# RTL8211.net
KiCad netlist of a schematic drawn in Altium Designer
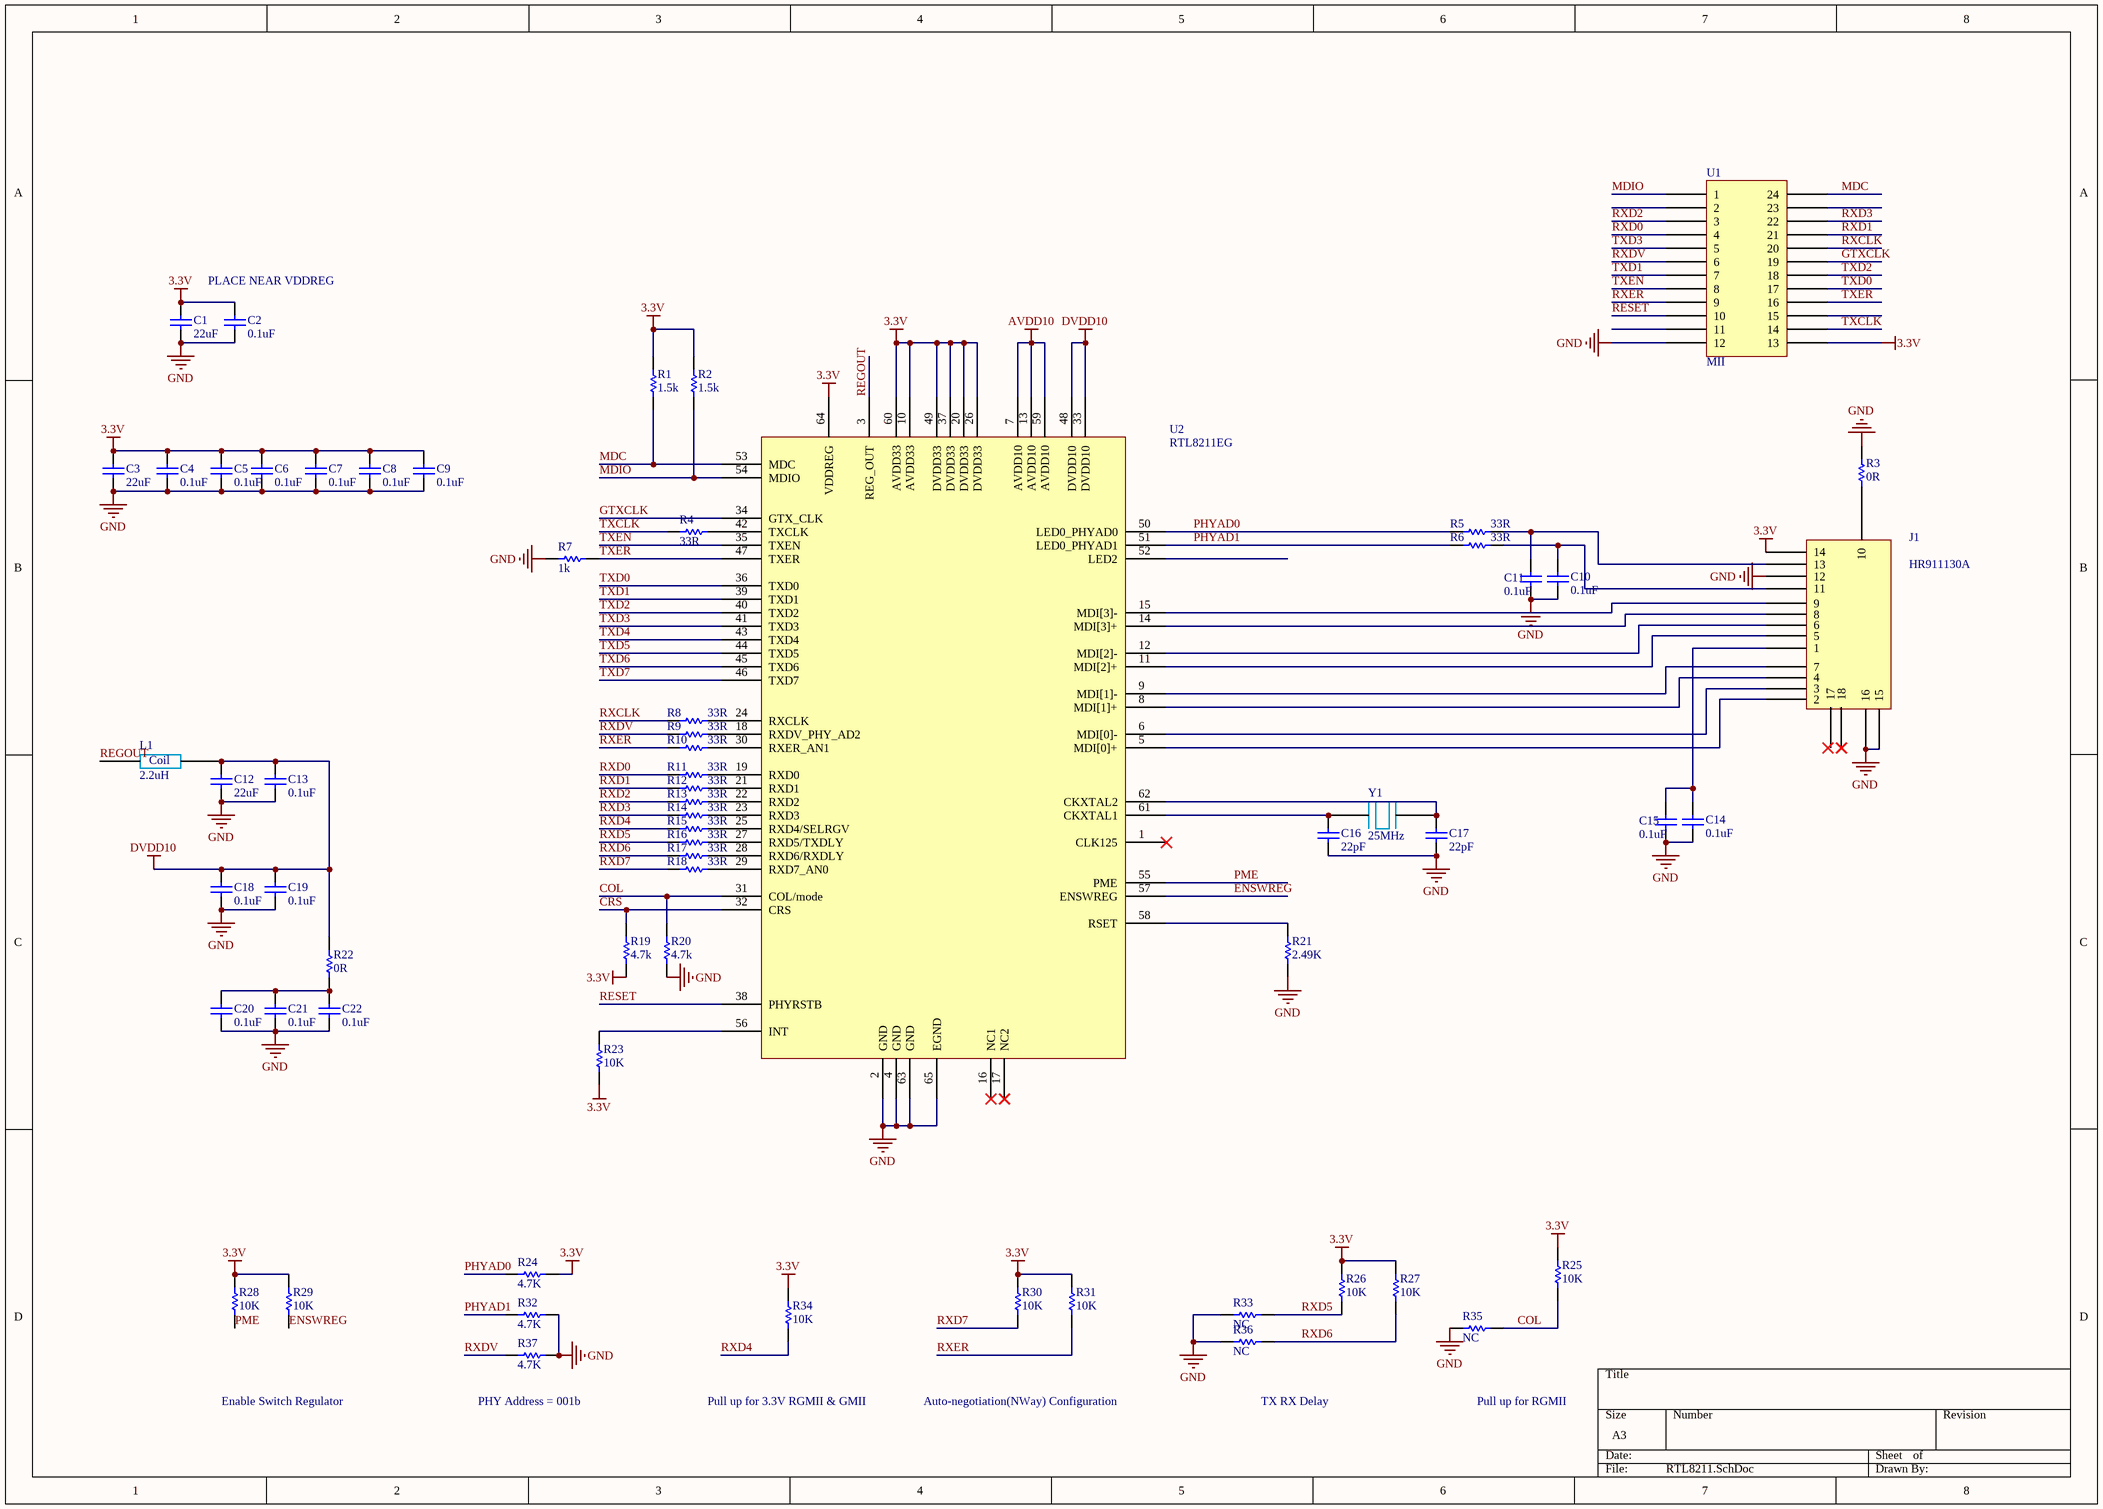
[diagram p0: RTL8211.SchDoc]

(export (version "E")
  (design (tool "Eeschema 10.0.6"))
  (components
    (comp (ref "C1")
      (value "22uF")
      (footprint "0805C")
      (description "Capacitor")
      (fields (field (name "PUBLISHER") "Altium Limited"))
      (libsource (lib "AutoCAN") (part "Cap"))
    )
    (comp (ref "C2")
      (value "0.1uF")
      (footprint "0805C")
      (description "Capacitor")
      (fields (field (name "PUBLISHER") "Altium Limited"))
      (libsource (lib "AutoCAN") (part "Cap"))
    )
    (comp (ref "C3")
      (value "22uF")
      (footprint "0805C")
      (description "Capacitor")
      (fields (field (name "PUBLISHER") "Altium Limited"))
      (libsource (lib "AutoCAN") (part "Cap"))
    )
    (comp (ref "C4")
      (value "0.1uF")
      (footprint "0805C")
      (description "Capacitor")
      (fields (field (name "PUBLISHER") "Altium Limited"))
      (libsource (lib "AutoCAN") (part "Cap"))
    )
    (comp (ref "C5")
      (value "0.1uF")
      (footprint "0805C")
      (description "Capacitor")
      (fields (field (name "PUBLISHER") "Altium Limited"))
      (libsource (lib "AutoCAN") (part "Cap"))
    )
    (comp (ref "C6")
      (value "0.1uF")
      (footprint "0805C")
      (description "Capacitor")
      (fields (field (name "PUBLISHER") "Altium Limited"))
      (libsource (lib "AutoCAN") (part "Cap"))
    )
    (comp (ref "C7")
      (value "0.1uF")
      (footprint "0805C")
      (description "Capacitor")
      (fields (field (name "PUBLISHER") "Altium Limited"))
      (libsource (lib "AutoCAN") (part "Cap"))
    )
    (comp (ref "C8")
      (value "0.1uF")
      (footprint "0805C")
      (description "Capacitor")
      (fields (field (name "PUBLISHER") "Altium Limited"))
      (libsource (lib "AutoCAN") (part "Cap"))
    )
    (comp (ref "C9")
      (value "0.1uF")
      (footprint "0805C")
      (description "Capacitor")
      (fields (field (name "PUBLISHER") "Altium Limited"))
      (libsource (lib "AutoCAN") (part "Cap"))
    )
    (comp (ref "C10")
      (value "0.1uF")
      (footprint "0805C")
      (description "Capacitor")
      (fields (field (name "PUBLISHER") "Altium Limited"))
      (libsource (lib "AutoCAN") (part "Cap"))
    )
    (comp (ref "C11")
      (value "0.1uF")
      (footprint "0805C")
      (description "Capacitor")
      (fields (field (name "PUBLISHER") "Altium Limited"))
      (libsource (lib "AutoCAN") (part "Cap"))
    )
    (comp (ref "C12")
      (value "22uF")
      (footprint "0805C")
      (description "Capacitor")
      (fields (field (name "PUBLISHER") "Altium Limited"))
      (libsource (lib "AutoCAN") (part "Cap"))
    )
    (comp (ref "C13")
      (value "0.1uF")
      (footprint "0805C")
      (description "Capacitor")
      (fields (field (name "PUBLISHER") "Altium Limited"))
      (libsource (lib "AutoCAN") (part "Cap"))
    )
    (comp (ref "C14")
      (value "0.1uF")
      (footprint "0805C")
      (description "Capacitor")
      (fields (field (name "PUBLISHER") "Altium Limited"))
      (libsource (lib "AutoCAN") (part "Cap"))
    )
    (comp (ref "C15")
      (value "0.1uF")
      (footprint "0805C")
      (description "Capacitor")
      (fields (field (name "PUBLISHER") "Altium Limited"))
      (libsource (lib "AutoCAN") (part "Cap"))
    )
    (comp (ref "C16")
      (value "22pF")
      (footprint "0805C")
      (description "Capacitor")
      (fields (field (name "PUBLISHER") "Altium Limited"))
      (libsource (lib "AutoCAN") (part "Cap"))
    )
    (comp (ref "C17")
      (value "22pF")
      (footprint "0805C")
      (description "Capacitor")
      (fields (field (name "PUBLISHER") "Altium Limited"))
      (libsource (lib "AutoCAN") (part "Cap"))
    )
    (comp (ref "C18")
      (value "0.1uF")
      (footprint "0805C")
      (description "Capacitor")
      (fields (field (name "PUBLISHER") "Altium Limited"))
      (libsource (lib "AutoCAN") (part "Cap"))
    )
    (comp (ref "C19")
      (value "0.1uF")
      (footprint "0805C")
      (description "Capacitor")
      (fields (field (name "PUBLISHER") "Altium Limited"))
      (libsource (lib "AutoCAN") (part "Cap"))
    )
    (comp (ref "C20")
      (value "0.1uF")
      (footprint "0805C")
      (description "Capacitor")
      (fields (field (name "PUBLISHER") "Altium Limited"))
      (libsource (lib "AutoCAN") (part "Cap"))
    )
    (comp (ref "C21")
      (value "0.1uF")
      (footprint "0805C")
      (description "Capacitor")
      (fields (field (name "PUBLISHER") "Altium Limited"))
      (libsource (lib "AutoCAN") (part "Cap"))
    )
    (comp (ref "C22")
      (value "0.1uF")
      (footprint "0805C")
      (description "Capacitor")
      (fields (field (name "PUBLISHER") "Altium Limited"))
      (libsource (lib "AutoCAN") (part "Cap"))
    )
    (comp (ref "J1")
      (value "HR911130A")
      (footprint "HR911130A")
      (libsource (lib "RTL8211EG") (part "HR911130A"))
    )
    (comp (ref "L1") (value "2.2uH") (footprint "Coil") (libsource (lib "RTL8211EG") (part "Coil")))
    (comp (ref "R1")
      (value "1.5k")
      (footprint "0805")
      (description "Resistor")
      (fields (field (name "Comment") "Res") (field (name "PUBLISHER") "Altium Limited"))
      (libsource (lib "AutoCAN") (part "Res"))
    )
    (comp (ref "R2")
      (value "1.5k")
      (footprint "0805")
      (description "Resistor")
      (fields (field (name "Comment") "Res") (field (name "PUBLISHER") "Altium Limited"))
      (libsource (lib "AutoCAN") (part "Res"))
    )
    (comp (ref "R3")
      (value "0R")
      (footprint "0805")
      (description "Resistor")
      (fields (field (name "Comment") "Res") (field (name "PUBLISHER") "Altium Limited"))
      (libsource (lib "AutoCAN") (part "Res"))
    )
    (comp (ref "R4")
      (value "33R")
      (footprint "0805")
      (description "Resistor")
      (fields (field (name "Comment") "Res") (field (name "PUBLISHER") "Altium Limited"))
      (libsource (lib "AutoCAN") (part "Res"))
    )
    (comp (ref "R5")
      (value "33R")
      (footprint "0805")
      (description "Resistor")
      (fields (field (name "Comment") "Res") (field (name "PUBLISHER") "Altium Limited"))
      (libsource (lib "AutoCAN") (part "Res"))
    )
    (comp (ref "R6")
      (value "33R")
      (footprint "0805")
      (description "Resistor")
      (fields (field (name "Comment") "Res") (field (name "PUBLISHER") "Altium Limited"))
      (libsource (lib "AutoCAN") (part "Res"))
    )
    (comp (ref "R7")
      (value "1k")
      (footprint "0805")
      (description "Resistor")
      (fields (field (name "Comment") "Res") (field (name "PUBLISHER") "Altium Limited"))
      (libsource (lib "AutoCAN") (part "Res"))
    )
    (comp (ref "R8")
      (value "33R")
      (footprint "0805")
      (description "Resistor")
      (fields (field (name "Comment") "Res") (field (name "PUBLISHER") "Altium Limited"))
      (libsource (lib "AutoCAN") (part "Res"))
    )
    (comp (ref "R9")
      (value "33R")
      (footprint "0805")
      (description "Resistor")
      (fields (field (name "Comment") "Res") (field (name "PUBLISHER") "Altium Limited"))
      (libsource (lib "AutoCAN") (part "Res"))
    )
    (comp (ref "R10")
      (value "33R")
      (footprint "0805")
      (description "Resistor")
      (fields (field (name "Comment") "Res") (field (name "PUBLISHER") "Altium Limited"))
      (libsource (lib "AutoCAN") (part "Res"))
    )
    (comp (ref "R11")
      (value "33R")
      (footprint "0805")
      (description "Resistor")
      (fields (field (name "Comment") "Res") (field (name "PUBLISHER") "Altium Limited"))
      (libsource (lib "AutoCAN") (part "Res"))
    )
    (comp (ref "R12")
      (value "33R")
      (footprint "0805")
      (description "Resistor")
      (fields (field (name "Comment") "Res") (field (name "PUBLISHER") "Altium Limited"))
      (libsource (lib "AutoCAN") (part "Res"))
    )
    (comp (ref "R13")
      (value "33R")
      (footprint "0805")
      (description "Resistor")
      (fields (field (name "Comment") "Res") (field (name "PUBLISHER") "Altium Limited"))
      (libsource (lib "AutoCAN") (part "Res"))
    )
    (comp (ref "R14")
      (value "33R")
      (footprint "0805")
      (description "Resistor")
      (fields (field (name "Comment") "Res") (field (name "PUBLISHER") "Altium Limited"))
      (libsource (lib "AutoCAN") (part "Res"))
    )
    (comp (ref "R15")
      (value "33R")
      (footprint "0805")
      (description "Resistor")
      (fields (field (name "Comment") "Res") (field (name "PUBLISHER") "Altium Limited"))
      (libsource (lib "AutoCAN") (part "Res"))
    )
    (comp (ref "R16")
      (value "33R")
      (footprint "0805")
      (description "Resistor")
      (fields (field (name "Comment") "Res") (field (name "PUBLISHER") "Altium Limited"))
      (libsource (lib "AutoCAN") (part "Res"))
    )
    (comp (ref "R17")
      (value "33R")
      (footprint "0805")
      (description "Resistor")
      (fields (field (name "Comment") "Res") (field (name "PUBLISHER") "Altium Limited"))
      (libsource (lib "AutoCAN") (part "Res"))
    )
    (comp (ref "R18")
      (value "33R")
      (footprint "0805")
      (description "Resistor")
      (fields (field (name "Comment") "Res") (field (name "PUBLISHER") "Altium Limited"))
      (libsource (lib "AutoCAN") (part "Res"))
    )
    (comp (ref "R19")
      (value "4.7k")
      (footprint "0805")
      (description "Resistor")
      (fields (field (name "Comment") "Res") (field (name "PUBLISHER") "Altium Limited"))
      (libsource (lib "AutoCAN") (part "Res"))
    )
    (comp (ref "R20")
      (value "4.7k")
      (footprint "0805")
      (description "Resistor")
      (fields (field (name "Comment") "Res") (field (name "PUBLISHER") "Altium Limited"))
      (libsource (lib "AutoCAN") (part "Res"))
    )
    (comp (ref "R21")
      (value "2.49K")
      (footprint "0805")
      (description "Resistor")
      (fields (field (name "Comment") "Res") (field (name "PUBLISHER") "Altium Limited"))
      (libsource (lib "AutoCAN") (part "Res"))
    )
    (comp (ref "R22")
      (value "0R")
      (footprint "0805")
      (description "Resistor")
      (fields (field (name "Comment") "Res") (field (name "PUBLISHER") "Altium Limited"))
      (libsource (lib "AutoCAN") (part "Res"))
    )
    (comp (ref "R23")
      (value "10K")
      (footprint "0805")
      (description "Resistor")
      (fields (field (name "Comment") "Res") (field (name "PUBLISHER") "Altium Limited"))
      (libsource (lib "AutoCAN") (part "Res"))
    )
    (comp (ref "R24")
      (value "4.7K")
      (footprint "0805")
      (description "Resistor")
      (fields (field (name "Comment") "Res") (field (name "PUBLISHER") "Altium Limited"))
      (libsource (lib "AutoCAN") (part "Res"))
    )
    (comp (ref "R25")
      (value "10K")
      (footprint "0805")
      (description "Resistor")
      (fields (field (name "Comment") "Res") (field (name "PUBLISHER") "Altium Limited"))
      (libsource (lib "AutoCAN") (part "Res"))
    )
    (comp (ref "R26")
      (value "10K")
      (footprint "0805")
      (description "Resistor")
      (fields (field (name "Comment") "Res") (field (name "PUBLISHER") "Altium Limited"))
      (libsource (lib "AutoCAN") (part "Res"))
    )
    (comp (ref "R27")
      (value "10K")
      (footprint "0805")
      (description "Resistor")
      (fields (field (name "Comment") "Res") (field (name "PUBLISHER") "Altium Limited"))
      (libsource (lib "AutoCAN") (part "Res"))
    )
    (comp (ref "R28")
      (value "10K")
      (footprint "0805")
      (description "Resistor")
      (fields (field (name "Comment") "Res") (field (name "PUBLISHER") "Altium Limited"))
      (libsource (lib "AutoCAN") (part "Res"))
    )
    (comp (ref "R29")
      (value "10K")
      (footprint "0805")
      (description "Resistor")
      (fields (field (name "Comment") "Res") (field (name "PUBLISHER") "Altium Limited"))
      (libsource (lib "AutoCAN") (part "Res"))
    )
    (comp (ref "R30")
      (value "10K")
      (footprint "0805")
      (description "Resistor")
      (fields (field (name "Comment") "Res") (field (name "PUBLISHER") "Altium Limited"))
      (libsource (lib "AutoCAN") (part "Res"))
    )
    (comp (ref "R31")
      (value "10K")
      (footprint "0805")
      (description "Resistor")
      (fields (field (name "Comment") "Res") (field (name "PUBLISHER") "Altium Limited"))
      (libsource (lib "AutoCAN") (part "Res"))
    )
    (comp (ref "R32")
      (value "4.7K")
      (footprint "0805")
      (description "Resistor")
      (fields (field (name "Comment") "Res") (field (name "PUBLISHER") "Altium Limited"))
      (libsource (lib "AutoCAN") (part "Res"))
    )
    (comp (ref "R33")
      (value "NC")
      (footprint "0805")
      (description "Resistor")
      (fields (field (name "Comment") "Res") (field (name "PUBLISHER") "Altium Limited"))
      (libsource (lib "AutoCAN") (part "Res"))
    )
    (comp (ref "R34")
      (value "10K")
      (footprint "0805")
      (description "Resistor")
      (fields (field (name "Comment") "Res") (field (name "PUBLISHER") "Altium Limited"))
      (libsource (lib "AutoCAN") (part "Res"))
    )
    (comp (ref "R35")
      (value "NC")
      (footprint "0805")
      (description "Resistor")
      (fields (field (name "Comment") "Res") (field (name "PUBLISHER") "Altium Limited"))
      (libsource (lib "AutoCAN") (part "Res"))
    )
    (comp (ref "R36")
      (value "NC")
      (footprint "0805")
      (description "Resistor")
      (fields (field (name "Comment") "Res") (field (name "PUBLISHER") "Altium Limited"))
      (libsource (lib "AutoCAN") (part "Res"))
    )
    (comp (ref "R37")
      (value "4.7K")
      (footprint "0805")
      (description "Resistor")
      (fields (field (name "Comment") "Res") (field (name "PUBLISHER") "Altium Limited"))
      (libsource (lib "AutoCAN") (part "Res"))
    )
    (comp (ref "U1") (value "MII") (footprint "MII") (libsource (lib "RTL8211EG") (part "MII")))
    (comp (ref "U2")
      (value "RTL8211EG")
      (footprint "RTL8211EGQFN")
      (libsource (lib "RTL8211EG") (part "RTL8211EG"))
    )
    (comp (ref "Y1") (value "25MHz") (footprint "XTAL") (libsource (lib "RTL8211EG") (part "XTAL")))
  )
  (nets
    (net (code "1") (name "/COL") (class "Default")
      (node (ref "R20") (pin "1") (pinfunction "1_1") (pintype "passive"))
      (node (ref "R25") (pin "2") (pinfunction "2_2") (pintype "passive"))
      (node (ref "R35") (pin "2") (pinfunction "2_2") (pintype "passive"))
      (node (ref "U2") (pin "31") (pinfunction "COL/mode_31") (pintype "passive"))
    )
    (net (code "2") (name "/CRS") (class "Default")
      (node (ref "R19") (pin "1") (pinfunction "1_1") (pintype "passive"))
      (node (ref "U2") (pin "32") (pinfunction "CRS_32") (pintype "passive"))
    )
    (net (code "3") (name "/ENSWREG") (class "Default")
      (node (ref "R29") (pin "2") (pinfunction "2_2") (pintype "passive"))
      (node (ref "U2") (pin "57") (pinfunction "ENSWREG_57") (pintype "passive"))
    )
    (net (code "4") (name "/GTXCLK") (class "Default")
      (node (ref "U1") (pin "19") (pinfunction "19_19") (pintype "passive"))
      (node (ref "U2") (pin "34") (pinfunction "GTX_CLK_34") (pintype "passive"))
    )
    (net (code "5") (name "/MDC") (class "Default")
      (node (ref "R1") (pin "1") (pinfunction "1_1") (pintype "passive"))
      (node (ref "U1") (pin "24") (pinfunction "24_24") (pintype "passive"))
      (node (ref "U2") (pin "53") (pinfunction "MDC_53") (pintype "passive"))
    )
    (net (code "6") (name "/MDIO") (class "Default")
      (node (ref "R2") (pin "1") (pinfunction "1_1") (pintype "passive"))
      (node (ref "U1") (pin "1") (pinfunction "1_1") (pintype "passive"))
      (node (ref "U2") (pin "54") (pinfunction "MDIO_54") (pintype "passive"))
    )
    (net (code "7") (name "/PHYAD0") (class "Default")
      (node (ref "R24") (pin "1") (pinfunction "1_1") (pintype "passive"))
      (node (ref "R5") (pin "2") (pinfunction "2_2") (pintype "passive"))
      (node (ref "U2") (pin "50") (pinfunction "LED0_PHYAD0_50") (pintype "passive"))
    )
    (net (code "8") (name "/PHYAD1") (class "Default")
      (node (ref "R32") (pin "1") (pinfunction "1_1") (pintype "passive"))
      (node (ref "R6") (pin "2") (pinfunction "2_2") (pintype "passive"))
      (node (ref "U2") (pin "51") (pinfunction "LED0_PHYAD1_51") (pintype "passive"))
    )
    (net (code "9") (name "/PME") (class "Default")
      (node (ref "R28") (pin "2") (pinfunction "2_2") (pintype "passive"))
      (node (ref "U2") (pin "55") (pinfunction "PME_55") (pintype "passive"))
    )
    (net (code "10") (name "/REGOUT") (class "Default")
      (node (ref "L1") (pin "1") (pinfunction "1_1") (pintype "passive"))
      (node (ref "U2") (pin "3") (pinfunction "REG_OUT_3") (pintype "passive"))
    )
    (net (code "11") (name "/RESET") (class "Default")
      (node (ref "U1") (pin "10") (pinfunction "10_10") (pintype "passive"))
      (node (ref "U2") (pin "38") (pinfunction "PHYRSTB_38") (pintype "passive"))
    )
    (net (code "12") (name "/RXCLK") (class "Default")
      (node (ref "R8") (pin "2") (pinfunction "2_2") (pintype "passive"))
      (node (ref "U1") (pin "20") (pinfunction "20_20") (pintype "passive"))
    )
    (net (code "13") (name "/RXD0") (class "Default")
      (node (ref "R11") (pin "2") (pinfunction "2_2") (pintype "passive"))
      (node (ref "U1") (pin "4") (pinfunction "4_4") (pintype "passive"))
    )
    (net (code "14") (name "/RXD1") (class "Default")
      (node (ref "R12") (pin "2") (pinfunction "2_2") (pintype "passive"))
      (node (ref "U1") (pin "21") (pinfunction "21_21") (pintype "passive"))
    )
    (net (code "15") (name "/RXD2") (class "Default")
      (node (ref "R13") (pin "2") (pinfunction "2_2") (pintype "passive"))
      (node (ref "U1") (pin "3") (pinfunction "3_3") (pintype "passive"))
    )
    (net (code "16") (name "/RXD3") (class "Default")
      (node (ref "R14") (pin "2") (pinfunction "2_2") (pintype "passive"))
      (node (ref "U1") (pin "22") (pinfunction "22_22") (pintype "passive"))
    )
    (net (code "17") (name "/RXD4") (class "Default")
      (node (ref "R15") (pin "2") (pinfunction "2_2") (pintype "passive"))
      (node (ref "R34") (pin "2") (pinfunction "2_2") (pintype "passive"))
    )
    (net (code "18") (name "/RXD5") (class "Default")
      (node (ref "R16") (pin "2") (pinfunction "2_2") (pintype "passive"))
      (node (ref "R26") (pin "2") (pinfunction "2_2") (pintype "passive"))
      (node (ref "R33") (pin "2") (pinfunction "2_2") (pintype "passive"))
    )
    (net (code "19") (name "/RXD6") (class "Default")
      (node (ref "R17") (pin "2") (pinfunction "2_2") (pintype "passive"))
      (node (ref "R27") (pin "2") (pinfunction "2_2") (pintype "passive"))
      (node (ref "R36") (pin "2") (pinfunction "2_2") (pintype "passive"))
    )
    (net (code "20") (name "/RXD7") (class "Default")
      (node (ref "R18") (pin "2") (pinfunction "2_2") (pintype "passive"))
      (node (ref "R30") (pin "2") (pinfunction "2_2") (pintype "passive"))
    )
    (net (code "21") (name "/RXDV") (class "Default")
      (node (ref "R37") (pin "1") (pinfunction "1_1") (pintype "passive"))
      (node (ref "R9") (pin "2") (pinfunction "2_2") (pintype "passive"))
      (node (ref "U1") (pin "6") (pinfunction "6_6") (pintype "passive"))
    )
    (net (code "22") (name "/RXER") (class "Default")
      (node (ref "R10") (pin "2") (pinfunction "2_2") (pintype "passive"))
      (node (ref "R31") (pin "2") (pinfunction "2_2") (pintype "passive"))
      (node (ref "U1") (pin "9") (pinfunction "9_9") (pintype "passive"))
    )
    (net (code "23") (name "/TXCLK") (class "Default")
      (node (ref "R4") (pin "2") (pinfunction "2_2") (pintype "passive"))
      (node (ref "U1") (pin "14") (pinfunction "14_14") (pintype "passive"))
    )
    (net (code "24") (name "/TXD0") (class "Default")
      (node (ref "U1") (pin "17") (pinfunction "17_17") (pintype "passive"))
      (node (ref "U2") (pin "36") (pinfunction "TXD0_36") (pintype "passive"))
    )
    (net (code "25") (name "/TXD1") (class "Default")
      (node (ref "U1") (pin "7") (pinfunction "7_7") (pintype "passive"))
      (node (ref "U2") (pin "39") (pinfunction "TXD1_39") (pintype "passive"))
    )
    (net (code "26") (name "/TXD2") (class "Default")
      (node (ref "U1") (pin "18") (pinfunction "18_18") (pintype "passive"))
      (node (ref "U2") (pin "40") (pinfunction "TXD2_40") (pintype "passive"))
    )
    (net (code "27") (name "/TXD3") (class "Default")
      (node (ref "U1") (pin "5") (pinfunction "5_5") (pintype "passive"))
      (node (ref "U2") (pin "41") (pinfunction "TXD3_41") (pintype "passive"))
    )
    (net (code "28") (name "/TXD4") (class "Default")
      (node (ref "U2") (pin "43") (pinfunction "TXD4_43") (pintype "passive"))
    )
    (net (code "29") (name "/TXD5") (class "Default")
      (node (ref "U2") (pin "44") (pinfunction "TXD5_44") (pintype "passive"))
    )
    (net (code "30") (name "/TXD6") (class "Default")
      (node (ref "U2") (pin "45") (pinfunction "TXD6_45") (pintype "passive"))
    )
    (net (code "31") (name "/TXD7") (class "Default")
      (node (ref "U2") (pin "46") (pinfunction "TXD7_46") (pintype "passive"))
    )
    (net (code "32") (name "/TXEN") (class "Default")
      (node (ref "U1") (pin "8") (pinfunction "8_8") (pintype "passive"))
      (node (ref "U2") (pin "35") (pinfunction "TXEN_35") (pintype "passive"))
    )
    (net (code "33") (name "/TXER") (class "Default")
      (node (ref "R7") (pin "1") (pinfunction "1_1") (pintype "passive"))
      (node (ref "U1") (pin "16") (pinfunction "16_16") (pintype "passive"))
      (node (ref "U2") (pin "47") (pinfunction "TXER_47") (pintype "passive"))
    )
    (net (code "34") (name "3.3V") (class "Default")
      (node (ref "C1") (pin "2") (pinfunction "2_2") (pintype "passive"))
      (node (ref "C2") (pin "2") (pinfunction "2_2") (pintype "passive"))
      (node (ref "C3") (pin "2") (pinfunction "2_2") (pintype "passive"))
      (node (ref "C4") (pin "2") (pinfunction "2_2") (pintype "passive"))
      (node (ref "C5") (pin "2") (pinfunction "2_2") (pintype "passive"))
      (node (ref "C6") (pin "2") (pinfunction "2_2") (pintype "passive"))
      (node (ref "C7") (pin "2") (pinfunction "2_2") (pintype "passive"))
      (node (ref "C8") (pin "2") (pinfunction "2_2") (pintype "passive"))
      (node (ref "C9") (pin "2") (pinfunction "2_2") (pintype "passive"))
      (node (ref "J1") (pin "14") (pinfunction "14_14") (pintype "passive"))
      (node (ref "R1") (pin "2") (pinfunction "2_2") (pintype "passive"))
      (node (ref "R19") (pin "2") (pinfunction "2_2") (pintype "passive"))
      (node (ref "R2") (pin "2") (pinfunction "2_2") (pintype "passive"))
      (node (ref "R23") (pin "2") (pinfunction "2_2") (pintype "passive"))
      (node (ref "R24") (pin "2") (pinfunction "2_2") (pintype "passive"))
      (node (ref "R25") (pin "1") (pinfunction "1_1") (pintype "passive"))
      (node (ref "R26") (pin "1") (pinfunction "1_1") (pintype "passive"))
      (node (ref "R27") (pin "1") (pinfunction "1_1") (pintype "passive"))
      (node (ref "R28") (pin "1") (pinfunction "1_1") (pintype "passive"))
      (node (ref "R29") (pin "1") (pinfunction "1_1") (pintype "passive"))
      (node (ref "R30") (pin "1") (pinfunction "1_1") (pintype "passive"))
      (node (ref "R31") (pin "1") (pinfunction "1_1") (pintype "passive"))
      (node (ref "R34") (pin "1") (pinfunction "1_1") (pintype "passive"))
      (node (ref "U1") (pin "13") (pinfunction "13_13") (pintype "passive"))
      (node (ref "U2") (pin "10") (pinfunction "AVDD33_10") (pintype "passive"))
      (node (ref "U2") (pin "20") (pinfunction "DVDD33_20") (pintype "passive"))
      (node (ref "U2") (pin "26") (pinfunction "DVDD33_26") (pintype "passive"))
      (node (ref "U2") (pin "37") (pinfunction "DVDD33_37") (pintype "passive"))
      (node (ref "U2") (pin "49") (pinfunction "DVDD33_49") (pintype "passive"))
      (node (ref "U2") (pin "60") (pinfunction "AVDD33_60") (pintype "passive"))
      (node (ref "U2") (pin "64") (pinfunction "VDDREG_64") (pintype "passive"))
    )
    (net (code "35") (name "AVDD10") (class "Default")
      (node (ref "U2") (pin "13") (pinfunction "AVDD10_13") (pintype "passive"))
      (node (ref "U2") (pin "59") (pinfunction "AVDD10_59") (pintype "passive"))
      (node (ref "U2") (pin "7") (pinfunction "AVDD10_7") (pintype "passive"))
    )
    (net (code "36") (name "DVDD10") (class "Default")
      (node (ref "C12") (pin "2") (pinfunction "2_2") (pintype "passive"))
      (node (ref "C13") (pin "2") (pinfunction "2_2") (pintype "passive"))
      (node (ref "C18") (pin "2") (pinfunction "2_2") (pintype "passive"))
      (node (ref "C19") (pin "2") (pinfunction "2_2") (pintype "passive"))
      (node (ref "L1") (pin "2") (pinfunction "2_2") (pintype "passive"))
      (node (ref "R22") (pin "1") (pinfunction "1_1") (pintype "passive"))
      (node (ref "U2") (pin "33") (pinfunction "DVDD10_33") (pintype "passive"))
      (node (ref "U2") (pin "48") (pinfunction "DVDD10_48") (pintype "passive"))
    )
    (net (code "37") (name "GND") (class "Default")
      (node (ref "C1") (pin "1") (pinfunction "1_1") (pintype "passive"))
      (node (ref "C10") (pin "1") (pinfunction "1_1") (pintype "passive"))
      (node (ref "C11") (pin "1") (pinfunction "1_1") (pintype "passive"))
      (node (ref "C12") (pin "1") (pinfunction "1_1") (pintype "passive"))
      (node (ref "C13") (pin "1") (pinfunction "1_1") (pintype "passive"))
      (node (ref "C14") (pin "1") (pinfunction "1_1") (pintype "passive"))
      (node (ref "C15") (pin "1") (pinfunction "1_1") (pintype "passive"))
      (node (ref "C16") (pin "1") (pinfunction "1_1") (pintype "passive"))
      (node (ref "C17") (pin "1") (pinfunction "1_1") (pintype "passive"))
      (node (ref "C18") (pin "1") (pinfunction "1_1") (pintype "passive"))
      (node (ref "C19") (pin "1") (pinfunction "1_1") (pintype "passive"))
      (node (ref "C2") (pin "1") (pinfunction "1_1") (pintype "passive"))
      (node (ref "C20") (pin "1") (pinfunction "1_1") (pintype "passive"))
      (node (ref "C21") (pin "1") (pinfunction "1_1") (pintype "passive"))
      (node (ref "C22") (pin "1") (pinfunction "1_1") (pintype "passive"))
      (node (ref "C3") (pin "1") (pinfunction "1_1") (pintype "passive"))
      (node (ref "C4") (pin "1") (pinfunction "1_1") (pintype "passive"))
      (node (ref "C5") (pin "1") (pinfunction "1_1") (pintype "passive"))
      (node (ref "C6") (pin "1") (pinfunction "1_1") (pintype "passive"))
      (node (ref "C7") (pin "1") (pinfunction "1_1") (pintype "passive"))
      (node (ref "C8") (pin "1") (pinfunction "1_1") (pintype "passive"))
      (node (ref "C9") (pin "1") (pinfunction "1_1") (pintype "passive"))
      (node (ref "J1") (pin "12") (pinfunction "12_12") (pintype "passive"))
      (node (ref "J1") (pin "15") (pinfunction "15_15") (pintype "passive"))
      (node (ref "J1") (pin "16") (pinfunction "16_16") (pintype "passive"))
      (node (ref "R20") (pin "2") (pinfunction "2_2") (pintype "passive"))
      (node (ref "R21") (pin "2") (pinfunction "2_2") (pintype "passive"))
      (node (ref "R3") (pin "1") (pinfunction "1_1") (pintype "passive"))
      (node (ref "R32") (pin "2") (pinfunction "2_2") (pintype "passive"))
      (node (ref "R33") (pin "1") (pinfunction "1_1") (pintype "passive"))
      (node (ref "R35") (pin "1") (pinfunction "1_1") (pintype "passive"))
      (node (ref "R36") (pin "1") (pinfunction "1_1") (pintype "passive"))
      (node (ref "R37") (pin "2") (pinfunction "2_2") (pintype "passive"))
      (node (ref "R7") (pin "2") (pinfunction "2_2") (pintype "passive"))
      (node (ref "U1") (pin "12") (pinfunction "12_12") (pintype "passive"))
      (node (ref "U2") (pin "2") (pinfunction "GND_2") (pintype "passive"))
      (node (ref "U2") (pin "4") (pinfunction "GND_4") (pintype "passive"))
      (node (ref "U2") (pin "63") (pinfunction "GND_63") (pintype "passive"))
      (node (ref "U2") (pin "65") (pinfunction "EGND_65") (pintype "passive"))
    )
    (net (code "38") (name "Net-(C10-Pad2)") (class "Default")
      (node (ref "C10") (pin "2") (pinfunction "2_2") (pintype "passive"))
      (node (ref "J1") (pin "11") (pinfunction "11_11") (pintype "passive"))
      (node (ref "R6") (pin "1") (pinfunction "1_1") (pintype "passive"))
    )
    (net (code "39") (name "Net-(C11-Pad2)") (class "Default")
      (node (ref "C11") (pin "2") (pinfunction "2_2") (pintype "passive"))
      (node (ref "J1") (pin "13") (pinfunction "13_13") (pintype "passive"))
      (node (ref "R5") (pin "1") (pinfunction "1_1") (pintype "passive"))
    )
    (net (code "40") (name "Net-(C14-Pad2)") (class "Default")
      (node (ref "C14") (pin "2") (pinfunction "2_2") (pintype "passive"))
      (node (ref "C15") (pin "2") (pinfunction "2_2") (pintype "passive"))
      (node (ref "J1") (pin "1") (pinfunction "1_1") (pintype "passive"))
    )
    (net (code "41") (name "Net-(C20-Pad2)") (class "Default")
      (node (ref "C20") (pin "2") (pinfunction "2_2") (pintype "passive"))
      (node (ref "C21") (pin "2") (pinfunction "2_2") (pintype "passive"))
      (node (ref "C22") (pin "2") (pinfunction "2_2") (pintype "passive"))
      (node (ref "R22") (pin "2") (pinfunction "2_2") (pintype "passive"))
    )
    (net (code "42") (name "Net-(J1-Pad10)") (class "Default")
      (node (ref "J1") (pin "10") (pinfunction "10_10") (pintype "passive"))
      (node (ref "R3") (pin "2") (pinfunction "2_2") (pintype "passive"))
    )
    (net (code "43") (name "Net-(U2-CKXTAL1)") (class "Default")
      (node (ref "C16") (pin "2") (pinfunction "2_2") (pintype "passive"))
      (node (ref "U2") (pin "61") (pinfunction "CKXTAL1_61") (pintype "passive"))
      (node (ref "Y1") (pin "1") (pinfunction "1_1") (pintype "passive"))
    )
    (net (code "44") (name "Net-(U2-CKXTAL2)") (class "Default")
      (node (ref "C17") (pin "2") (pinfunction "2_2") (pintype "passive"))
      (node (ref "U2") (pin "62") (pinfunction "CKXTAL2_62") (pintype "passive"))
      (node (ref "Y1") (pin "2") (pinfunction "2_2") (pintype "passive"))
    )
    (net (code "45") (name "Net-(U2-INT)") (class "Default")
      (node (ref "R23") (pin "1") (pinfunction "1_1") (pintype "passive"))
      (node (ref "U2") (pin "56") (pinfunction "INT_56") (pintype "passive"))
    )
    (net (code "46") (name "Net-(U2-MDI[0]+)") (class "Default")
      (node (ref "J1") (pin "2") (pinfunction "2_2") (pintype "passive"))
      (node (ref "U2") (pin "5") (pinfunction "MDI[0]+_5") (pintype "passive"))
    )
    (net (code "47") (name "Net-(U2-MDI[0]-)") (class "Default")
      (node (ref "J1") (pin "3") (pinfunction "3_3") (pintype "passive"))
      (node (ref "U2") (pin "6") (pinfunction "MDI[0]-_6") (pintype "passive"))
    )
    (net (code "48") (name "Net-(U2-MDI[1]+)") (class "Default")
      (node (ref "J1") (pin "4") (pinfunction "4_4") (pintype "passive"))
      (node (ref "U2") (pin "8") (pinfunction "MDI[1]+_8") (pintype "passive"))
    )
    (net (code "49") (name "Net-(U2-MDI[1]-)") (class "Default")
      (node (ref "J1") (pin "7") (pinfunction "7_7") (pintype "passive"))
      (node (ref "U2") (pin "9") (pinfunction "MDI[1]-_9") (pintype "passive"))
    )
    (net (code "50") (name "Net-(U2-MDI[2]+)") (class "Default")
      (node (ref "J1") (pin "5") (pinfunction "5_5") (pintype "passive"))
      (node (ref "U2") (pin "11") (pinfunction "MDI[2]+_11") (pintype "passive"))
    )
    (net (code "51") (name "Net-(U2-MDI[2]-)") (class "Default")
      (node (ref "J1") (pin "6") (pinfunction "6_6") (pintype "passive"))
      (node (ref "U2") (pin "12") (pinfunction "MDI[2]-_12") (pintype "passive"))
    )
    (net (code "52") (name "Net-(U2-MDI[3]+)") (class "Default")
      (node (ref "J1") (pin "8") (pinfunction "8_8") (pintype "passive"))
      (node (ref "U2") (pin "14") (pinfunction "MDI[3]+_14") (pintype "passive"))
    )
    (net (code "53") (name "Net-(U2-MDI[3]-)") (class "Default")
      (node (ref "J1") (pin "9") (pinfunction "9_9") (pintype "passive"))
      (node (ref "U2") (pin "15") (pinfunction "MDI[3]-_15") (pintype "passive"))
    )
    (net (code "54") (name "Net-(U2-RSET)") (class "Default")
      (node (ref "R21") (pin "1") (pinfunction "1_1") (pintype "passive"))
      (node (ref "U2") (pin "58") (pinfunction "RSET_58") (pintype "passive"))
    )
    (net (code "55") (name "Net-(U2-RXCLK)") (class "Default")
      (node (ref "R8") (pin "1") (pinfunction "1_1") (pintype "passive"))
      (node (ref "U2") (pin "24") (pinfunction "RXCLK_24") (pintype "passive"))
    )
    (net (code "56") (name "Net-(U2-RXD0)") (class "Default")
      (node (ref "R11") (pin "1") (pinfunction "1_1") (pintype "passive"))
      (node (ref "U2") (pin "19") (pinfunction "RXD0_19") (pintype "passive"))
    )
    (net (code "57") (name "Net-(U2-RXD1)") (class "Default")
      (node (ref "R12") (pin "1") (pinfunction "1_1") (pintype "passive"))
      (node (ref "U2") (pin "21") (pinfunction "RXD1_21") (pintype "passive"))
    )
    (net (code "58") (name "Net-(U2-RXD2)") (class "Default")
      (node (ref "R13") (pin "1") (pinfunction "1_1") (pintype "passive"))
      (node (ref "U2") (pin "22") (pinfunction "RXD2_22") (pintype "passive"))
    )
    (net (code "59") (name "Net-(U2-RXD3)") (class "Default")
      (node (ref "R14") (pin "1") (pinfunction "1_1") (pintype "passive"))
      (node (ref "U2") (pin "23") (pinfunction "RXD3_23") (pintype "passive"))
    )
    (net (code "60") (name "Net-(U2-RXD4{slash}SELRGV)") (class "Default")
      (node (ref "R15") (pin "1") (pinfunction "1_1") (pintype "passive"))
      (node (ref "U2") (pin "25") (pinfunction "RXD4/SELRGV_25") (pintype "passive"))
    )
    (net (code "61") (name "Net-(U2-RXD5{slash}TXDLY)") (class "Default")
      (node (ref "R16") (pin "1") (pinfunction "1_1") (pintype "passive"))
      (node (ref "U2") (pin "27") (pinfunction "RXD5/TXDLY_27") (pintype "passive"))
    )
    (net (code "62") (name "Net-(U2-RXD6{slash}RXDLY)") (class "Default")
      (node (ref "R17") (pin "1") (pinfunction "1_1") (pintype "passive"))
      (node (ref "U2") (pin "28") (pinfunction "RXD6/RXDLY_28") (pintype "passive"))
    )
    (net (code "63") (name "Net-(U2-RXD7_AN0)") (class "Default")
      (node (ref "R18") (pin "1") (pinfunction "1_1") (pintype "passive"))
      (node (ref "U2") (pin "29") (pinfunction "RXD7_AN0_29") (pintype "passive"))
    )
    (net (code "64") (name "Net-(U2-RXDV_PHY_AD2)") (class "Default")
      (node (ref "R9") (pin "1") (pinfunction "1_1") (pintype "passive"))
      (node (ref "U2") (pin "18") (pinfunction "RXDV_PHY_AD2_18") (pintype "passive"))
    )
    (net (code "65") (name "Net-(U2-RXER_AN1)") (class "Default")
      (node (ref "R10") (pin "1") (pinfunction "1_1") (pintype "passive"))
      (node (ref "U2") (pin "30") (pinfunction "RXER_AN1_30") (pintype "passive"))
    )
    (net (code "66") (name "Net-(U2-TXCLK)") (class "Default")
      (node (ref "R4") (pin "1") (pinfunction "1_1") (pintype "passive"))
      (node (ref "U2") (pin "42") (pinfunction "TXCLK_42") (pintype "passive"))
    )
    (net (code "67") (name "unconnected-(J1-Pad17)") (class "Default")
      (node (ref "J1") (pin "17") (pinfunction "17_17") (pintype "passive"))
    )
    (net (code "68") (name "unconnected-(J1-Pad18)") (class "Default")
      (node (ref "J1") (pin "18") (pinfunction "18_18") (pintype "passive+no_connect"))
    )
    (net (code "69") (name "unconnected-(U1-Pad2)") (class "Default")
      (node (ref "U1") (pin "2") (pinfunction "2_2") (pintype "passive"))
    )
    (net (code "70") (name "unconnected-(U1-Pad11)") (class "Default")
      (node (ref "U1") (pin "11") (pinfunction "11_11") (pintype "passive"))
    )
    (net (code "71") (name "unconnected-(U1-Pad15)") (class "Default")
      (node (ref "U1") (pin "15") (pinfunction "15_15") (pintype "passive"))
    )
    (net (code "72") (name "unconnected-(U1-Pad23)") (class "Default")
      (node (ref "U1") (pin "23") (pinfunction "23_23") (pintype "passive"))
    )
    (net (code "73") (name "unconnected-(U2-CLK125-Pad1)") (class "Default")
      (node (ref "U2") (pin "1") (pinfunction "CLK125_1") (pintype "passive+no_connect"))
    )
    (net (code "74") (name "unconnected-(U2-LED2-Pad52)") (class "Default")
      (node (ref "U2") (pin "52") (pinfunction "LED2_52") (pintype "passive"))
    )
    (net (code "75") (name "unconnected-(U2-NC1-Pad16)") (class "Default")
      (node (ref "U2") (pin "16") (pinfunction "NC1_16") (pintype "passive+no_connect"))
    )
    (net (code "76") (name "unconnected-(U2-NC2-Pad17)") (class "Default")
      (node (ref "U2") (pin "17") (pinfunction "NC2_17") (pintype "passive+no_connect"))
    )
  )
)
